# keyboard_project.net
KiCad netlist of a schematic drawn in EAGLE
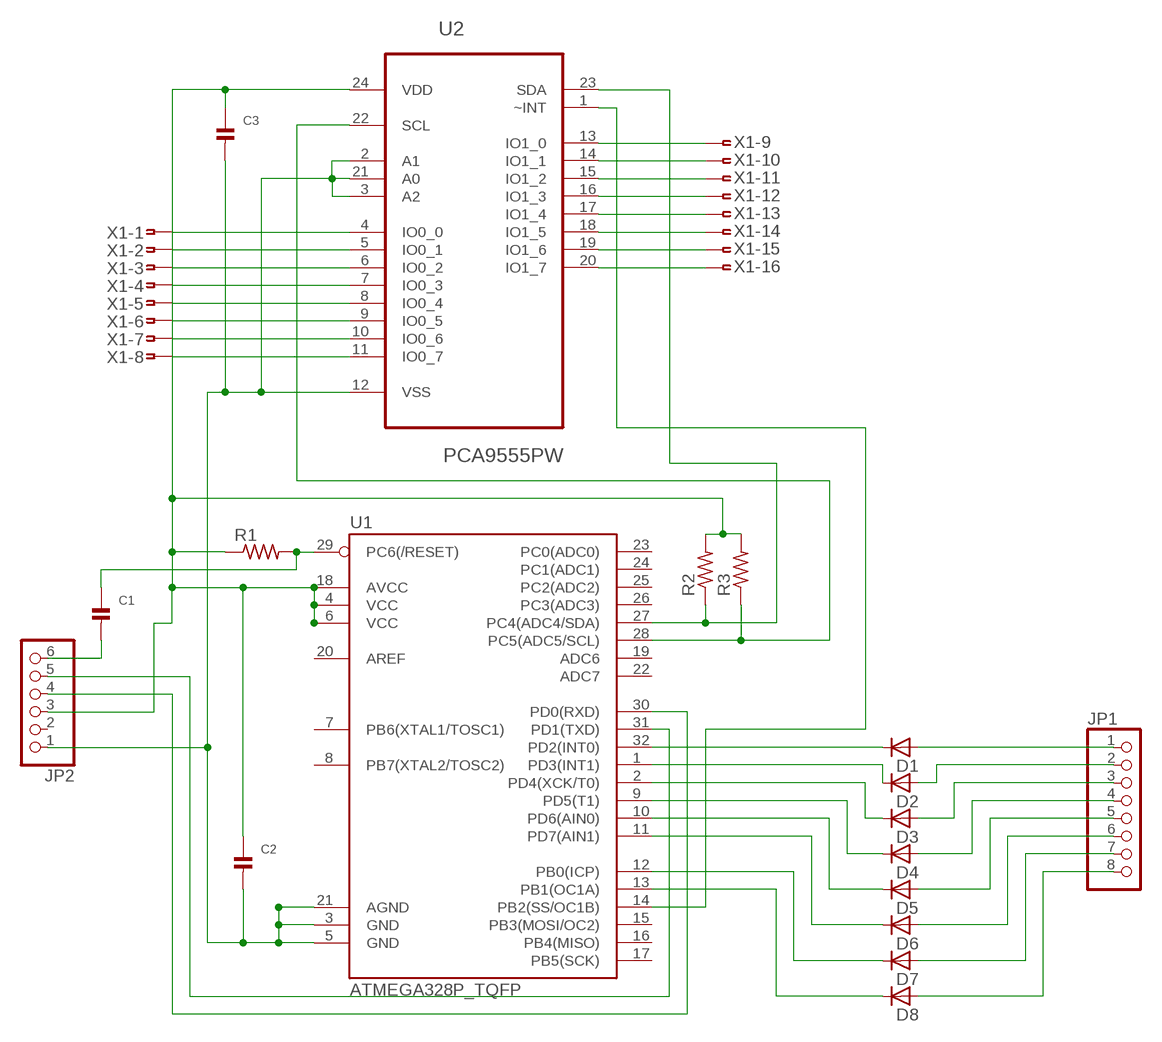
[diagram p0: schematic, sheet 1]

(export (version "E")
  (design (tool "Eeschema 10.0.6"))
  (components
    (comp (ref "C1")
      (value "CAP_CERAMIC0603")
      (footprint "eagle-import:0603")
      (libsource (lib "eagle-import") (part "CAP_CERAMIC0603"))
    )
    (comp (ref "C2")
      (value "CAP_CERAMIC0603")
      (footprint "eagle-import:0603")
      (libsource (lib "eagle-import") (part "CAP_CERAMIC0603"))
    )
    (comp (ref "C3")
      (value "CAP_CERAMIC0603")
      (footprint "eagle-import:0603")
      (libsource (lib "eagle-import") (part "CAP_CERAMIC0603"))
    )
    (comp (ref "D1")
      (value "D1N4148")
      (footprint "eagle-import:D45_2")
      (libsource (lib "eagle-import") (part "D1N4148"))
    )
    (comp (ref "D2")
      (value "D1N4148")
      (footprint "eagle-import:D45_2")
      (libsource (lib "eagle-import") (part "D1N4148"))
    )
    (comp (ref "D3")
      (value "D1N4148")
      (footprint "eagle-import:D45_2")
      (libsource (lib "eagle-import") (part "D1N4148"))
    )
    (comp (ref "D4")
      (value "D1N4148")
      (footprint "eagle-import:D45_2")
      (libsource (lib "eagle-import") (part "D1N4148"))
    )
    (comp (ref "D5")
      (value "D1N4148")
      (footprint "eagle-import:D45_2")
      (libsource (lib "eagle-import") (part "D1N4148"))
    )
    (comp (ref "D6")
      (value "D1N4148")
      (footprint "eagle-import:D45_2")
      (libsource (lib "eagle-import") (part "D1N4148"))
    )
    (comp (ref "D7")
      (value "D1N4148")
      (footprint "eagle-import:D45_2")
      (libsource (lib "eagle-import") (part "D1N4148"))
    )
    (comp (ref "D8")
      (value "D1N4148")
      (footprint "eagle-import:D45_2")
      (libsource (lib "eagle-import") (part "D1N4148"))
    )
    (comp (ref "JP1")
      (value "PINHD-1X8")
      (footprint "eagle-import:1X08")
      (libsource (lib "eagle-import") (part "PINHD-1X8"))
    )
    (comp (ref "JP2")
      (value "HEADER-1X6")
      (footprint "eagle-import:1X06_OVAL")
      (libsource (lib "eagle-import") (part "HEADER-1X6"))
    )
    (comp (ref "R1")
      (value "R-US_R0603")
      (footprint "eagle-import:R0603")
      (libsource (lib "eagle-import") (part "R-US_R0603"))
    )
    (comp (ref "R2")
      (value "R-US_R0603")
      (footprint "eagle-import:R0603")
      (libsource (lib "eagle-import") (part "R-US_R0603"))
    )
    (comp (ref "R3")
      (value "R-US_R0603")
      (footprint "eagle-import:R0603")
      (libsource (lib "eagle-import") (part "R-US_R0603"))
    )
    (comp (ref "U1")
      (value "ATMEGA328P_TQFP")
      (footprint "eagle-import:TQFP32-08")
      (libsource (lib "eagle-import") (part "ATMEGA328P_TQFP"))
    )
    (comp (ref "U2")
      (value "PCA9555PW")
      (footprint "eagle-import:SOP65P640X110-24N")
      (libsource (lib "eagle-import") (part "PCA9555PW"))
    )
    (comp (ref "X1")
      (value "FTOP-16")
      (footprint "eagle-import:FTOP-16")
      (libsource (lib "eagle-import") (part "FTOP-16"))
    )
  )
  (nets
    (net (code "1") (name "Net-(C1-P$1)") (class "Default")
      (node (ref "C1") (pin "1") (pinfunction "P$1_1") (pintype "passive"))
      (node (ref "R1") (pin "2") (pinfunction "2_2") (pintype "passive"))
      (node (ref "U1") (pin "29") (pinfunction "PC6(/RESET)_29") (pintype "bidirectional"))
    )
    (net (code "2") (name "Net-(C1-P$2)") (class "Default")
      (node (ref "C1") (pin "2") (pinfunction "P$2_2") (pintype "passive"))
      (node (ref "JP2") (pin "6") (pinfunction "6_6") (pintype "passive"))
    )
    (net (code "3") (name "Net-(C2-P$1)") (class "Default")
      (node (ref "C2") (pin "1") (pinfunction "P$1_1") (pintype "passive"))
      (node (ref "C3") (pin "1") (pinfunction "P$1_1") (pintype "passive"))
      (node (ref "JP2") (pin "3") (pinfunction "3_3") (pintype "passive"))
      (node (ref "R1") (pin "1") (pinfunction "1_1") (pintype "passive"))
      (node (ref "R2") (pin "2") (pinfunction "2_2") (pintype "passive"))
      (node (ref "R3") (pin "2") (pinfunction "2_2") (pintype "passive"))
      (node (ref "U1") (pin "18") (pinfunction "AVCC_18") (pintype "bidirectional"))
      (node (ref "U1") (pin "4") (pinfunction "VCC_4") (pintype "bidirectional"))
      (node (ref "U1") (pin "6") (pinfunction "VCC_6") (pintype "bidirectional"))
      (node (ref "U2") (pin "24") (pinfunction "VDD_24") (pintype "power_in"))
    )
    (net (code "4") (name "Net-(C2-P$2)") (class "Default")
      (node (ref "C2") (pin "2") (pinfunction "P$2_2") (pintype "passive"))
      (node (ref "C3") (pin "2") (pinfunction "P$2_2") (pintype "passive"))
      (node (ref "JP2") (pin "1") (pinfunction "1_1") (pintype "passive"))
      (node (ref "U1") (pin "21") (pinfunction "AGND_21") (pintype "bidirectional"))
      (node (ref "U1") (pin "3") (pinfunction "GND_3") (pintype "bidirectional"))
      (node (ref "U1") (pin "5") (pinfunction "GND_5") (pintype "bidirectional"))
      (node (ref "U2") (pin "12") (pinfunction "VSS_12") (pintype "passive"))
      (node (ref "U2") (pin "2") (pinfunction "A1_2") (pintype "input"))
      (node (ref "U2") (pin "21") (pinfunction "A0_21") (pintype "input"))
      (node (ref "U2") (pin "3") (pinfunction "A2_3") (pintype "input"))
    )
    (net (code "5") (name "Net-(D1-PadA)") (class "Default")
      (node (ref "D1") (pin "A") (pinfunction "A_A") (pintype "passive"))
      (node (ref "JP1") (pin "1") (pinfunction "1_1") (pintype "passive"))
    )
    (net (code "6") (name "Net-(D2-PadA)") (class "Default")
      (node (ref "D2") (pin "A") (pinfunction "A_A") (pintype "passive"))
      (node (ref "JP1") (pin "2") (pinfunction "2_2") (pintype "passive"))
    )
    (net (code "7") (name "Net-(D3-PadA)") (class "Default")
      (node (ref "D3") (pin "A") (pinfunction "A_A") (pintype "passive"))
      (node (ref "JP1") (pin "3") (pinfunction "3_3") (pintype "passive"))
    )
    (net (code "8") (name "Net-(D4-PadA)") (class "Default")
      (node (ref "D4") (pin "A") (pinfunction "A_A") (pintype "passive"))
      (node (ref "JP1") (pin "4") (pinfunction "4_4") (pintype "passive"))
    )
    (net (code "9") (name "Net-(D5-PadA)") (class "Default")
      (node (ref "D5") (pin "A") (pinfunction "A_A") (pintype "passive"))
      (node (ref "JP1") (pin "5") (pinfunction "5_5") (pintype "passive"))
    )
    (net (code "10") (name "Net-(D6-PadA)") (class "Default")
      (node (ref "D6") (pin "A") (pinfunction "A_A") (pintype "passive"))
      (node (ref "JP1") (pin "6") (pinfunction "6_6") (pintype "passive"))
    )
    (net (code "11") (name "Net-(D7-PadA)") (class "Default")
      (node (ref "D7") (pin "A") (pinfunction "A_A") (pintype "passive"))
      (node (ref "JP1") (pin "7") (pinfunction "7_7") (pintype "passive"))
    )
    (net (code "12") (name "Net-(D8-PadA)") (class "Default")
      (node (ref "D8") (pin "A") (pinfunction "A_A") (pintype "passive"))
      (node (ref "JP1") (pin "8") (pinfunction "8_8") (pintype "passive"))
    )
    (net (code "13") (name "Net-(U1-PB0(ICP))") (class "Default")
      (node (ref "D7") (pin "C") (pinfunction "C_C") (pintype "passive"))
      (node (ref "U1") (pin "12") (pinfunction "PB0(ICP)_12") (pintype "bidirectional"))
    )
    (net (code "14") (name "Net-(U1-PB1(OC1A))") (class "Default")
      (node (ref "D8") (pin "C") (pinfunction "C_C") (pintype "passive"))
      (node (ref "U1") (pin "13") (pinfunction "PB1(OC1A)_13") (pintype "bidirectional"))
    )
    (net (code "15") (name "Net-(U1-PB2(SS{slash}OC1B))") (class "Default")
      (node (ref "U1") (pin "14") (pinfunction "PB2(SS/OC1B)_14") (pintype "bidirectional"))
      (node (ref "U2") (pin "1") (pinfunction "~{INT}_1") (pintype "output"))
    )
    (net (code "16") (name "Net-(U1-PC4(ADC4{slash}SDA))") (class "Default")
      (node (ref "R2") (pin "1") (pinfunction "1_1") (pintype "passive"))
      (node (ref "U1") (pin "27") (pinfunction "PC4(ADC4/SDA)_27") (pintype "bidirectional"))
      (node (ref "U2") (pin "23") (pinfunction "SDA_23") (pintype "bidirectional"))
    )
    (net (code "17") (name "Net-(U1-PC5(ADC5{slash}SCL))") (class "Default")
      (node (ref "R3") (pin "1") (pinfunction "1_1") (pintype "passive"))
      (node (ref "U1") (pin "28") (pinfunction "PC5(ADC5/SCL)_28") (pintype "bidirectional"))
      (node (ref "U2") (pin "22") (pinfunction "SCL_22") (pintype "input"))
    )
    (net (code "18") (name "Net-(U1-PD0(RXD))") (class "Default")
      (node (ref "JP2") (pin "4") (pinfunction "4_4") (pintype "passive"))
      (node (ref "U1") (pin "30") (pinfunction "PD0(RXD)_30") (pintype "bidirectional"))
    )
    (net (code "19") (name "Net-(U1-PD1(TXD))") (class "Default")
      (node (ref "JP2") (pin "5") (pinfunction "5_5") (pintype "passive"))
      (node (ref "U1") (pin "31") (pinfunction "PD1(TXD)_31") (pintype "bidirectional"))
    )
    (net (code "20") (name "Net-(U1-PD2(INT0))") (class "Default")
      (node (ref "D1") (pin "C") (pinfunction "C_C") (pintype "passive"))
      (node (ref "U1") (pin "32") (pinfunction "PD2(INT0)_32") (pintype "bidirectional"))
    )
    (net (code "21") (name "Net-(U1-PD3(INT1))") (class "Default")
      (node (ref "D2") (pin "C") (pinfunction "C_C") (pintype "passive"))
      (node (ref "U1") (pin "1") (pinfunction "PD3(INT1)_1") (pintype "bidirectional"))
    )
    (net (code "22") (name "Net-(U1-PD4(XCK{slash}T0))") (class "Default")
      (node (ref "D3") (pin "C") (pinfunction "C_C") (pintype "passive"))
      (node (ref "U1") (pin "2") (pinfunction "PD4(XCK/T0)_2") (pintype "bidirectional"))
    )
    (net (code "23") (name "Net-(U1-PD5(T1))") (class "Default")
      (node (ref "D4") (pin "C") (pinfunction "C_C") (pintype "passive"))
      (node (ref "U1") (pin "9") (pinfunction "PD5(T1)_9") (pintype "bidirectional"))
    )
    (net (code "24") (name "Net-(U1-PD6(AIN0))") (class "Default")
      (node (ref "D5") (pin "C") (pinfunction "C_C") (pintype "passive"))
      (node (ref "U1") (pin "10") (pinfunction "PD6(AIN0)_10") (pintype "bidirectional"))
    )
    (net (code "25") (name "Net-(U1-PD7(AIN1))") (class "Default")
      (node (ref "D6") (pin "C") (pinfunction "C_C") (pintype "passive"))
      (node (ref "U1") (pin "11") (pinfunction "PD7(AIN1)_11") (pintype "bidirectional"))
    )
    (net (code "26") (name "Net-(U2-IO0_0)") (class "Default")
      (node (ref "U2") (pin "4") (pinfunction "IO0_0_4") (pintype "bidirectional"))
      (node (ref "X1") (pin "1") (pinfunction "1_1") (pintype "passive"))
    )
    (net (code "27") (name "Net-(U2-IO0_1)") (class "Default")
      (node (ref "U2") (pin "5") (pinfunction "IO0_1_5") (pintype "bidirectional"))
      (node (ref "X1") (pin "2") (pinfunction "1_2") (pintype "passive"))
    )
    (net (code "28") (name "Net-(U2-IO0_2)") (class "Default")
      (node (ref "U2") (pin "6") (pinfunction "IO0_2_6") (pintype "bidirectional"))
      (node (ref "X1") (pin "3") (pinfunction "1_3") (pintype "passive"))
    )
    (net (code "29") (name "Net-(U2-IO0_3)") (class "Default")
      (node (ref "U2") (pin "7") (pinfunction "IO0_3_7") (pintype "bidirectional"))
      (node (ref "X1") (pin "4") (pinfunction "1_4") (pintype "passive"))
    )
    (net (code "30") (name "Net-(U2-IO0_4)") (class "Default")
      (node (ref "U2") (pin "8") (pinfunction "IO0_4_8") (pintype "bidirectional"))
      (node (ref "X1") (pin "5") (pinfunction "1_5") (pintype "passive"))
    )
    (net (code "31") (name "Net-(U2-IO0_5)") (class "Default")
      (node (ref "U2") (pin "9") (pinfunction "IO0_5_9") (pintype "bidirectional"))
      (node (ref "X1") (pin "6") (pinfunction "1_6") (pintype "passive"))
    )
    (net (code "32") (name "Net-(U2-IO0_6)") (class "Default")
      (node (ref "U2") (pin "10") (pinfunction "IO0_6_10") (pintype "bidirectional"))
      (node (ref "X1") (pin "7") (pinfunction "1_7") (pintype "passive"))
    )
    (net (code "33") (name "Net-(U2-IO0_7)") (class "Default")
      (node (ref "U2") (pin "11") (pinfunction "IO0_7_11") (pintype "bidirectional"))
      (node (ref "X1") (pin "8") (pinfunction "1_8") (pintype "passive"))
    )
    (net (code "34") (name "Net-(U2-IO1_0)") (class "Default")
      (node (ref "U2") (pin "13") (pinfunction "IO1_0_13") (pintype "bidirectional"))
      (node (ref "X1") (pin "9") (pinfunction "1_9") (pintype "passive"))
    )
    (net (code "35") (name "Net-(U2-IO1_1)") (class "Default")
      (node (ref "U2") (pin "14") (pinfunction "IO1_1_14") (pintype "bidirectional"))
      (node (ref "X1") (pin "10") (pinfunction "1_10") (pintype "passive"))
    )
    (net (code "36") (name "Net-(U2-IO1_2)") (class "Default")
      (node (ref "U2") (pin "15") (pinfunction "IO1_2_15") (pintype "bidirectional"))
      (node (ref "X1") (pin "11") (pinfunction "1_11") (pintype "passive"))
    )
    (net (code "37") (name "Net-(U2-IO1_3)") (class "Default")
      (node (ref "U2") (pin "16") (pinfunction "IO1_3_16") (pintype "bidirectional"))
      (node (ref "X1") (pin "12") (pinfunction "1_12") (pintype "passive"))
    )
    (net (code "38") (name "Net-(U2-IO1_4)") (class "Default")
      (node (ref "U2") (pin "17") (pinfunction "IO1_4_17") (pintype "bidirectional"))
      (node (ref "X1") (pin "13") (pinfunction "1_13") (pintype "passive"))
    )
    (net (code "39") (name "Net-(U2-IO1_5)") (class "Default")
      (node (ref "U2") (pin "18") (pinfunction "IO1_5_18") (pintype "bidirectional"))
      (node (ref "X1") (pin "14") (pinfunction "1_14") (pintype "passive"))
    )
    (net (code "40") (name "Net-(U2-IO1_6)") (class "Default")
      (node (ref "U2") (pin "19") (pinfunction "IO1_6_19") (pintype "bidirectional"))
      (node (ref "X1") (pin "15") (pinfunction "1_15") (pintype "passive"))
    )
    (net (code "41") (name "Net-(U2-IO1_7)") (class "Default")
      (node (ref "U2") (pin "20") (pinfunction "IO1_7_20") (pintype "bidirectional"))
      (node (ref "X1") (pin "16") (pinfunction "1_16") (pintype "passive"))
    )
    (net (code "42") (name "unconnected-(JP2-Pad2)") (class "Default")
      (node (ref "JP2") (pin "2") (pinfunction "2_2") (pintype "passive"))
    )
    (net (code "43") (name "unconnected-(U1-ADC6-Pad19)") (class "Default")
      (node (ref "U1") (pin "19") (pinfunction "ADC6_19") (pintype "bidirectional"))
    )
    (net (code "44") (name "unconnected-(U1-ADC7-Pad22)") (class "Default")
      (node (ref "U1") (pin "22") (pinfunction "ADC7_22") (pintype "bidirectional"))
    )
    (net (code "45") (name "unconnected-(U1-AREF-Pad20)") (class "Default")
      (node (ref "U1") (pin "20") (pinfunction "AREF_20") (pintype "bidirectional"))
    )
    (net (code "46") (name "unconnected-(U1-PB3(MOSI{slash}OC2)-Pad15)") (class "Default")
      (node (ref "U1") (pin "15") (pinfunction "PB3(MOSI/OC2)_15") (pintype "bidirectional"))
    )
    (net (code "47") (name "unconnected-(U1-PB4(MISO)-Pad16)") (class "Default")
      (node (ref "U1") (pin "16") (pinfunction "PB4(MISO)_16") (pintype "bidirectional"))
    )
    (net (code "48") (name "unconnected-(U1-PB5(SCK)-Pad17)") (class "Default")
      (node (ref "U1") (pin "17") (pinfunction "PB5(SCK)_17") (pintype "bidirectional"))
    )
    (net (code "49") (name "unconnected-(U1-PB6(XTAL1{slash}TOSC1)-Pad7)") (class "Default")
      (node (ref "U1") (pin "7") (pinfunction "PB6(XTAL1/TOSC1)_7") (pintype "bidirectional"))
    )
    (net (code "50") (name "unconnected-(U1-PB7(XTAL2{slash}TOSC2)-Pad8)") (class "Default")
      (node (ref "U1") (pin "8") (pinfunction "PB7(XTAL2/TOSC2)_8") (pintype "bidirectional"))
    )
    (net (code "51") (name "unconnected-(U1-PC0(ADC0)-Pad23)") (class "Default")
      (node (ref "U1") (pin "23") (pinfunction "PC0(ADC0)_23") (pintype "bidirectional"))
    )
    (net (code "52") (name "unconnected-(U1-PC1(ADC1)-Pad24)") (class "Default")
      (node (ref "U1") (pin "24") (pinfunction "PC1(ADC1)_24") (pintype "bidirectional"))
    )
    (net (code "53") (name "unconnected-(U1-PC2(ADC2)-Pad25)") (class "Default")
      (node (ref "U1") (pin "25") (pinfunction "PC2(ADC2)_25") (pintype "bidirectional"))
    )
    (net (code "54") (name "unconnected-(U1-PC3(ADC3)-Pad26)") (class "Default")
      (node (ref "U1") (pin "26") (pinfunction "PC3(ADC3)_26") (pintype "bidirectional"))
    )
  )
)
